# PickupBoard_2.net
KiCad netlist of a schematic drawn in EAGLE
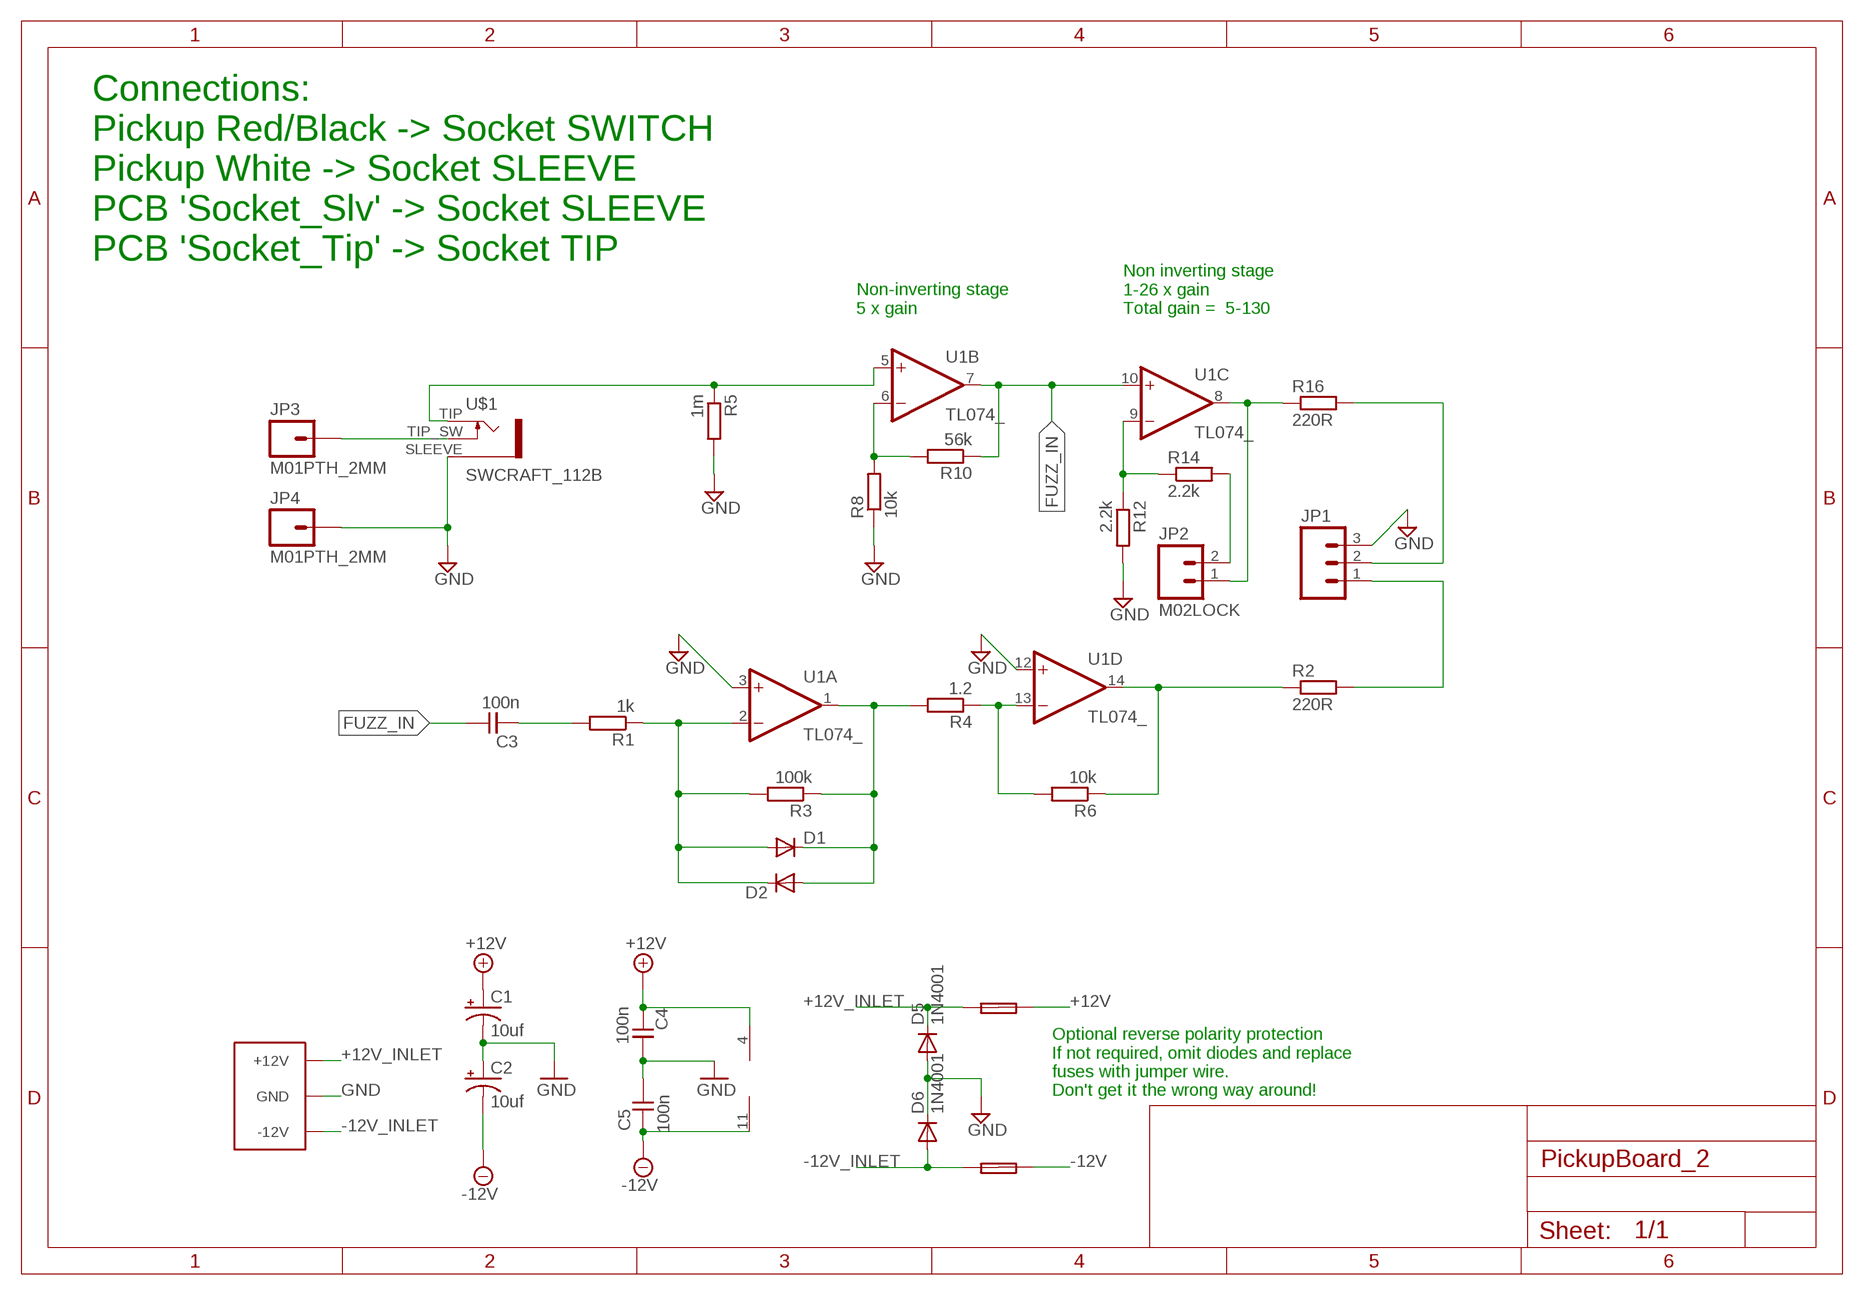
[diagram p0: schematic, sheet 1]

(export (version "E")
  (design (tool "Eeschema 10.0.6"))
  (components
    (comp (ref "1")
      (value "FUSE")
      (footprint "eagle-import:C050H075X075")
      (libsource (lib "eagle-import") (part "PTC_FUSEPOLY_FUSE"))
    )
    (comp (ref "C1")
      (value "10uf")
      (footprint "eagle-import:CPOL-RADIAL-10UF-25V")
      (libsource (lib "eagle-import") (part "CAP_POLPTH2"))
    )
    (comp (ref "C2")
      (value "10uf")
      (footprint "eagle-import:CPOL-RADIAL-10UF-25V")
      (libsource (lib "eagle-import") (part "CAP_POLPTH2"))
    )
    (comp (ref "C3")
      (value "100n")
      (footprint "eagle-import:C050-024X044")
      (libsource (lib "eagle-import") (part "C-EU050-024X044"))
    )
    (comp (ref "C4")
      (value "100n")
      (footprint "eagle-import:C050-024X044")
      (libsource (lib "eagle-import") (part "C-EU050-024X044"))
    )
    (comp (ref "C5")
      (value "100n")
      (footprint "eagle-import:C050-024X044")
      (libsource (lib "eagle-import") (part "C-EU050-024X044"))
    )
    (comp (ref "D1")
      (value "SMALL_DIODEDO35-7")
      (footprint "eagle-import:DO35-7")
      (libsource (lib "eagle-import") (part "SMALL_DIODEDO35-7"))
    )
    (comp (ref "D2")
      (value "SMALL_DIODEDO35-7")
      (footprint "eagle-import:DO35-7")
      (libsource (lib "eagle-import") (part "SMALL_DIODEDO35-7"))
    )
    (comp (ref "D5")
      (value "1N4001")
      (footprint "eagle-import:DO41-10")
      (libsource (lib "eagle-import") (part "1N4004"))
    )
    (comp (ref "D6")
      (value "1N4001")
      (footprint "eagle-import:DO41-10")
      (libsource (lib "eagle-import") (part "1N4004"))
    )
    (comp (ref "FUSE")
      (value "FUSE")
      (footprint "eagle-import:C050H075X075")
      (libsource (lib "eagle-import") (part "PTC_FUSEPOLY_FUSE"))
    )
    (comp (ref "JP1")
      (value "M03LOCK")
      (footprint "eagle-import:1X03_LOCK")
      (libsource (lib "eagle-import") (part "M03LOCK"))
    )
    (comp (ref "JP2")
      (value "M02LOCK")
      (footprint "eagle-import:1X02_LOCK")
      (libsource (lib "eagle-import") (part "M02LOCK"))
    )
    (comp (ref "JP3")
      (value "M01PTH_2MM")
      (footprint "eagle-import:1X01_2MM")
      (libsource (lib "eagle-import") (part "M01PTH_2MM"))
    )
    (comp (ref "JP4")
      (value "M01PTH_2MM")
      (footprint "eagle-import:1X01_2MM")
      (libsource (lib "eagle-import") (part "M01PTH_2MM"))
    )
    (comp (ref "R1")
      (value "1k")
      (footprint "eagle-import:7MM_RESISTOR")
      (libsource (lib "eagle-import") (part "RESISTOR7MM"))
    )
    (comp (ref "R2")
      (value "220R")
      (footprint "eagle-import:7MM_RESISTOR")
      (libsource (lib "eagle-import") (part "RESISTOR7MM"))
    )
    (comp (ref "R3")
      (value "100k")
      (footprint "eagle-import:7MM_RESISTOR")
      (libsource (lib "eagle-import") (part "RESISTOR7MM"))
    )
    (comp (ref "R4")
      (value "1.2")
      (footprint "eagle-import:7MM_RESISTOR")
      (libsource (lib "eagle-import") (part "RESISTOR7MM"))
    )
    (comp (ref "R5")
      (value "1m")
      (footprint "eagle-import:7MM_RESISTOR")
      (libsource (lib "eagle-import") (part "RESISTOR7MM"))
    )
    (comp (ref "R6")
      (value "10k")
      (footprint "eagle-import:7MM_RESISTOR")
      (libsource (lib "eagle-import") (part "RESISTOR7MM"))
    )
    (comp (ref "R8")
      (value "10k")
      (footprint "eagle-import:7MM_RESISTOR")
      (libsource (lib "eagle-import") (part "RESISTOR7MM"))
    )
    (comp (ref "R10")
      (value "56k")
      (footprint "eagle-import:7MM_RESISTOR")
      (libsource (lib "eagle-import") (part "RESISTOR7MM"))
    )
    (comp (ref "R12")
      (value "2.2k")
      (footprint "eagle-import:7MM_RESISTOR")
      (libsource (lib "eagle-import") (part "RESISTOR7MM"))
    )
    (comp (ref "R14")
      (value "2.2k")
      (footprint "eagle-import:7MM_RESISTOR")
      (libsource (lib "eagle-import") (part "RESISTOR7MM"))
    )
    (comp (ref "R16")
      (value "220R")
      (footprint "eagle-import:7MM_RESISTOR")
      (libsource (lib "eagle-import") (part "RESISTOR7MM"))
    )
    (comp (ref "U$1")
      (value "SWCRAFT_112B")
      (footprint "eagle-import:SWCRAFT_112_SLOTS")
      (libsource (lib "eagle-import") (part "SWCRAFT_112B"))
    )
    (comp (ref "U$2")
      (value "EURO_POWER_LOCK")
      (footprint "eagle-import:EURO_PWR_HEADER_LOCK")
      (libsource (lib "eagle-import") (part "EURO_POWER_LOCK"))
    )
    (comp (ref "U1")
      (value "TL074_")
      (footprint "eagle-import:DIL14")
      (libsource (lib "eagle-import") (part "TL074_"))
    )
  )
  (nets
    (net (code "1") (name "+12V") (class "Default")
      (node (ref "1") (pin "2") (pinfunction "P$2_2") (pintype "bidirectional"))
      (node (ref "C1") (pin "1") (pinfunction "+_1") (pintype "passive"))
      (node (ref "C4") (pin "2") (pinfunction "2_2") (pintype "passive"))
      (node (ref "U1") (pin "4") (pinfunction "V+_4") (pintype "power_in"))
    )
    (net (code "2") (name "-12V") (class "Default")
      (node (ref "C2") (pin "2") (pinfunction "-_2") (pintype "passive"))
      (node (ref "C5") (pin "2") (pinfunction "2_2") (pintype "passive"))
      (node (ref "FUSE") (pin "2") (pinfunction "P$2_2") (pintype "bidirectional"))
      (node (ref "U1") (pin "11") (pinfunction "V-_11") (pintype "power_in"))
    )
    (net (code "3") (name "/+12V_INLET") (class "Default")
      (node (ref "1") (pin "1") (pinfunction "P$1_1") (pintype "bidirectional"))
      (node (ref "D5") (pin "C") (pinfunction "C_C") (pintype "passive"))
      (node (ref "U$2") (pin "POS1") (pinfunction "+12V_POS1") (pintype "bidirectional"))
      (node (ref "U$2") (pin "POS2") (pinfunction "+12V_POS2") (pintype "bidirectional"))
    )
    (net (code "4") (name "/-12V_INLET") (class "Default")
      (node (ref "D6") (pin "A") (pinfunction "A_A") (pintype "passive"))
      (node (ref "FUSE") (pin "1") (pinfunction "P$1_1") (pintype "bidirectional"))
      (node (ref "U$2") (pin "NEG1") (pinfunction "-12V_NEG1") (pintype "bidirectional"))
      (node (ref "U$2") (pin "NEG2") (pinfunction "-12V_NEG2") (pintype "bidirectional"))
    )
    (net (code "5") (name "FUZZ_IN") (class "Default")
      (node (ref "C3") (pin "1") (pinfunction "1_1") (pintype "passive"))
      (node (ref "R10") (pin "1") (pinfunction "1_1") (pintype "passive"))
      (node (ref "U1") (pin "10") (pinfunction "+IN_10") (pintype "input"))
      (node (ref "U1") (pin "7") (pinfunction "OUT_7") (pintype "output"))
    )
    (net (code "6") (name "GND") (class "Default")
      (node (ref "C1") (pin "2") (pinfunction "-_2") (pintype "passive"))
      (node (ref "C2") (pin "1") (pinfunction "+_1") (pintype "passive"))
      (node (ref "C4") (pin "1") (pinfunction "1_1") (pintype "passive"))
      (node (ref "C5") (pin "1") (pinfunction "1_1") (pintype "passive"))
      (node (ref "D5") (pin "A") (pinfunction "A_A") (pintype "passive"))
      (node (ref "D6") (pin "C") (pinfunction "C_C") (pintype "passive"))
      (node (ref "JP1") (pin "3") (pinfunction "3_3") (pintype "passive"))
      (node (ref "JP4") (pin "1") (pinfunction "1_1") (pintype "passive"))
      (node (ref "R12") (pin "2") (pinfunction "2_2") (pintype "passive"))
      (node (ref "R5") (pin "2") (pinfunction "2_2") (pintype "passive"))
      (node (ref "R8") (pin "1") (pinfunction "1_1") (pintype "passive"))
      (node (ref "U$1") (pin "SLEEVE") (pinfunction "5_SLEEVE") (pintype "passive"))
      (node (ref "U$2") (pin "GND1") (pinfunction "GND_GND1") (pintype "bidirectional"))
      (node (ref "U$2") (pin "GND2") (pinfunction "GND_GND2") (pintype "bidirectional"))
      (node (ref "U$2") (pin "GND3") (pinfunction "GND_GND3") (pintype "bidirectional"))
      (node (ref "U$2") (pin "GND4") (pinfunction "GND_GND4") (pintype "bidirectional"))
      (node (ref "U$2") (pin "GND5") (pinfunction "GND_GND5") (pintype "bidirectional"))
      (node (ref "U$2") (pin "GND6") (pinfunction "GND_GND6") (pintype "bidirectional"))
      (node (ref "U1") (pin "12") (pinfunction "+IN_12") (pintype "input"))
      (node (ref "U1") (pin "3") (pinfunction "+IN_3") (pintype "input"))
    )
    (net (code "7") (name "Net-(C3-Pad2)") (class "Default")
      (node (ref "C3") (pin "2") (pinfunction "2_2") (pintype "passive"))
      (node (ref "R1") (pin "2") (pinfunction "2_2") (pintype "passive"))
    )
    (net (code "8") (name "Net-(JP1-Pad1)") (class "Default")
      (node (ref "JP1") (pin "1") (pinfunction "1_1") (pintype "passive"))
      (node (ref "R2") (pin "2") (pinfunction "2_2") (pintype "passive"))
    )
    (net (code "9") (name "Net-(JP1-Pad2)") (class "Default")
      (node (ref "JP1") (pin "2") (pinfunction "2_2") (pintype "passive"))
      (node (ref "R16") (pin "2") (pinfunction "2_2") (pintype "passive"))
    )
    (net (code "10") (name "Net-(JP2-Pad2)") (class "Default")
      (node (ref "JP2") (pin "2") (pinfunction "2_2") (pintype "passive"))
      (node (ref "R14") (pin "2") (pinfunction "2_2") (pintype "passive"))
    )
    (net (code "11") (name "Net-(U$1-3)") (class "Default")
      (node (ref "R5") (pin "1") (pinfunction "1_1") (pintype "passive"))
      (node (ref "U$1") (pin "TIP") (pinfunction "3_TIP") (pintype "passive"))
      (node (ref "U1") (pin "5") (pinfunction "+IN_5") (pintype "input"))
    )
    (net (code "12") (name "Net-(U$1-4)") (class "Default")
      (node (ref "JP3") (pin "1") (pinfunction "1_1") (pintype "passive"))
      (node (ref "U$1") (pin "TIP_SW") (pinfunction "4_TIP_SW") (pintype "passive"))
    )
    (net (code "13") (name "Net-(U1A--IN)") (class "Default")
      (node (ref "D1") (pin "A") (pinfunction "A_A") (pintype "passive"))
      (node (ref "D2") (pin "C") (pinfunction "C_C") (pintype "passive"))
      (node (ref "R1") (pin "1") (pinfunction "1_1") (pintype "passive"))
      (node (ref "R3") (pin "2") (pinfunction "2_2") (pintype "passive"))
      (node (ref "U1") (pin "2") (pinfunction "-IN_2") (pintype "input"))
    )
    (net (code "14") (name "Net-(U1A-OUT)") (class "Default")
      (node (ref "D1") (pin "C") (pinfunction "C_C") (pintype "passive"))
      (node (ref "D2") (pin "A") (pinfunction "A_A") (pintype "passive"))
      (node (ref "R3") (pin "1") (pinfunction "1_1") (pintype "passive"))
      (node (ref "R4") (pin "2") (pinfunction "2_2") (pintype "passive"))
      (node (ref "U1") (pin "1") (pinfunction "OUT_1") (pintype "output"))
    )
    (net (code "15") (name "Net-(U1B--IN)") (class "Default")
      (node (ref "R10") (pin "2") (pinfunction "2_2") (pintype "passive"))
      (node (ref "R8") (pin "2") (pinfunction "2_2") (pintype "passive"))
      (node (ref "U1") (pin "6") (pinfunction "-IN_6") (pintype "input"))
    )
    (net (code "16") (name "Net-(U1C--IN)") (class "Default")
      (node (ref "R12") (pin "1") (pinfunction "1_1") (pintype "passive"))
      (node (ref "R14") (pin "1") (pinfunction "1_1") (pintype "passive"))
      (node (ref "U1") (pin "9") (pinfunction "-IN_9") (pintype "input"))
    )
    (net (code "17") (name "Net-(U1C-OUT)") (class "Default")
      (node (ref "JP2") (pin "1") (pinfunction "1_1") (pintype "passive"))
      (node (ref "R16") (pin "1") (pinfunction "1_1") (pintype "passive"))
      (node (ref "U1") (pin "8") (pinfunction "OUT_8") (pintype "output"))
    )
    (net (code "18") (name "Net-(U1D--IN)") (class "Default")
      (node (ref "R4") (pin "1") (pinfunction "1_1") (pintype "passive"))
      (node (ref "R6") (pin "2") (pinfunction "2_2") (pintype "passive"))
      (node (ref "U1") (pin "13") (pinfunction "-IN_13") (pintype "input"))
    )
    (net (code "19") (name "Net-(U1D-OUT)") (class "Default")
      (node (ref "R2") (pin "1") (pinfunction "1_1") (pintype "passive"))
      (node (ref "R6") (pin "1") (pinfunction "1_1") (pintype "passive"))
      (node (ref "U1") (pin "14") (pinfunction "OUT_14") (pintype "output"))
    )
  )
)
